# ZHSD-POWER.net
KiCad netlist of a schematic drawn in Altium Designer
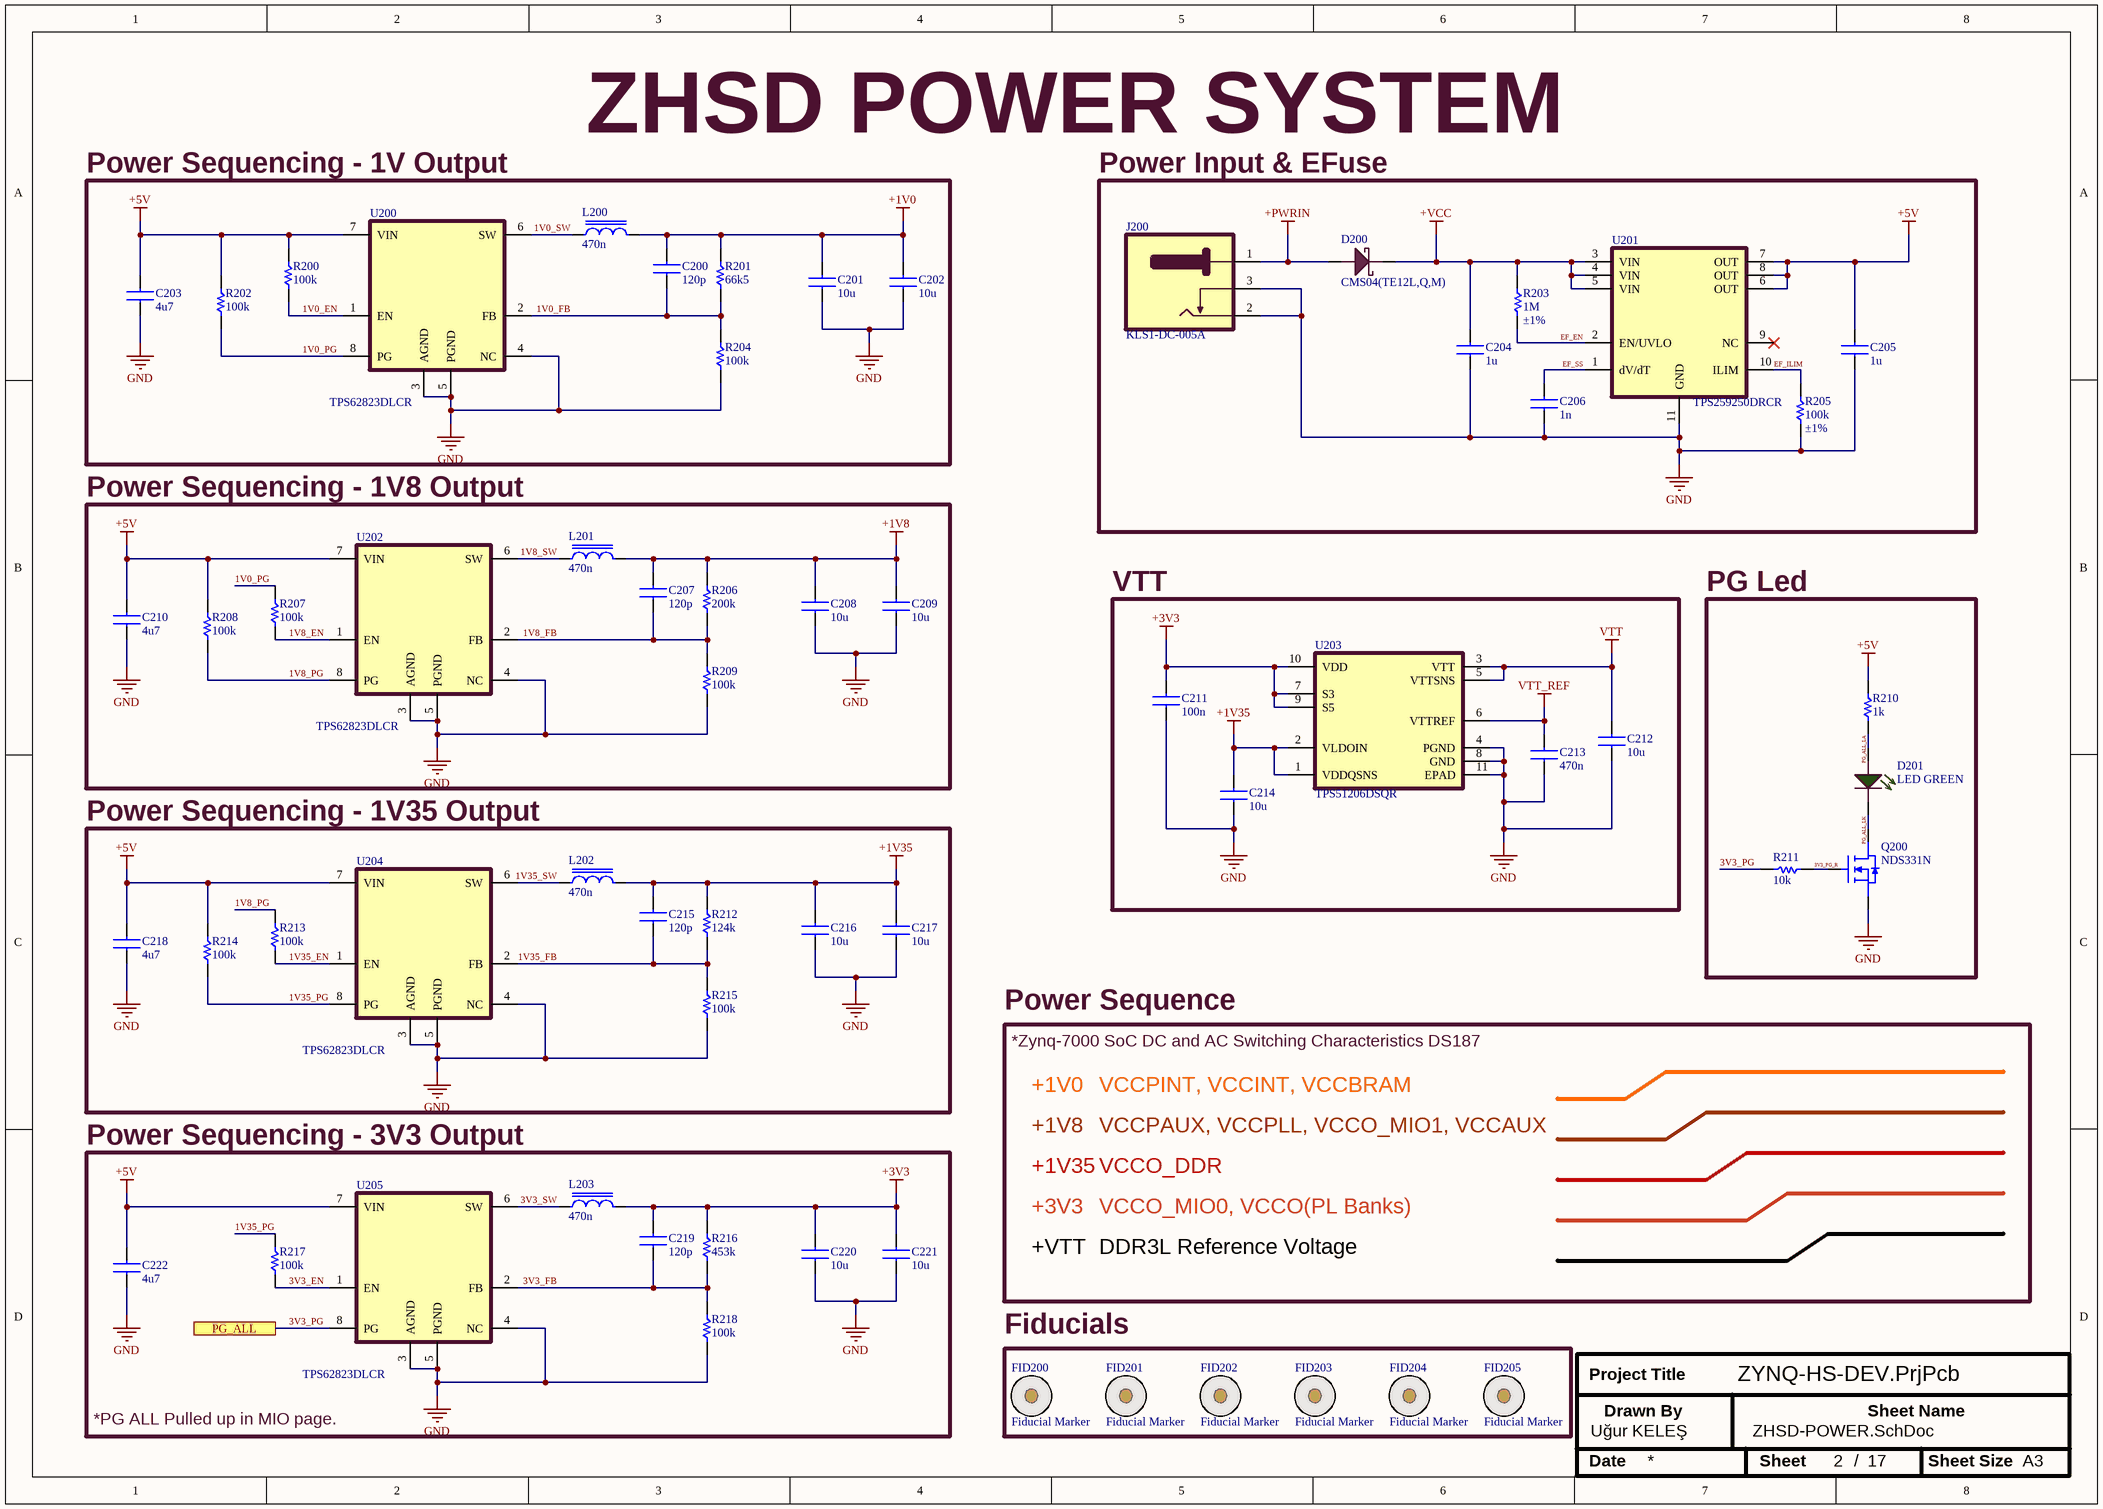
[diagram p0: ZHSD-POWER.SchDoc]

(export (version "E")
  (design (tool "Eeschema 10.0.6"))
  (components
    (comp (ref "C200")
      (value "120p")
      (footprint "0603CAPC1608X09N")
      (description "CAP CER 120PF 50V C0G/NP0 0603 (1608) ±5%")
      (fields (field (name "MANUFACTURER") "Murata Electronics") (field (name "MPN") "GRM1885C1H121JA01D"))
      (libsource (lib "UK_Library") (part "GRM1885C1H121JA01D"))
    )
    (comp (ref "C201")
      (value "10u")
      (footprint "0603CAPC1608X09N")
      (description "CAP CER 10UF 10V X7R 0603 (1608) ±20%")
      (fields (field (name "MANUFACTURER") "Murata Electronics") (field (name "MPN") "GRM188Z71A106MA73D"))
      (libsource (lib "UK_Library") (part "GRM188Z71A106MA73D"))
    )
    (comp (ref "C202")
      (value "10u")
      (footprint "0603CAPC1608X09N")
      (description "CAP CER 10UF 10V X7R 0603 (1608) ±20%")
      (fields (field (name "MANUFACTURER") "Murata Electronics") (field (name "MPN") "GRM188Z71A106MA73D"))
      (libsource (lib "UK_Library") (part "GRM188Z71A106MA73D"))
    )
    (comp (ref "C203")
      (value "4u7")
      (footprint "0805CAPC2012X14N")
      (description "CAP CER 4.7UF 10V X7R 0805 (2012) ±10%")
      (fields (field (name "MANUFACTURER") "Murata Electronics") (field (name "MPN") "GRM21BR71A475KE51L"))
      (libsource (lib "UK_Library") (part "GRM21BR71A475KE51L"))
    )
    (comp (ref "C204")
      (value "1u")
      (footprint "0603CAPC1608X09N")
      (description "CAP CER 1UF 25V X5R 0603 (1608) ±10%")
      (fields
        (field (name "MANUFACTURER") "Murata Power Solutions Inc.")
        (field (name "MPN") "GRM188R61E105KA12D")
      )
      (libsource (lib "UK_Library") (part "GRM188R61E105KA12D"))
    )
    (comp (ref "C205")
      (value "1u")
      (footprint "0603CAPC1608X09N")
      (description "CAP CER 1UF 25V X5R 0603 (1608) ±10%")
      (fields
        (field (name "MANUFACTURER") "Murata Power Solutions Inc.")
        (field (name "MPN") "GRM188R61E105KA12D")
      )
      (libsource (lib "UK_Library") (part "GRM188R61E105KA12D"))
    )
    (comp (ref "C206")
      (value "1n")
      (footprint "0603CAPC1608X09N")
      (description "CAP CER 1000PF 50V X7R 0603 (1608) ±10%")
      (fields (field (name "MANUFACTURER") "Murata Electronics") (field (name "MPN") "GCM188R71H102KA37D"))
      (libsource (lib "UK_Library") (part "GCM188R71H102KA37D"))
    )
    (comp (ref "C207")
      (value "120p")
      (footprint "0603CAPC1608X09N")
      (description "CAP CER 120PF 50V C0G/NP0 0603 (1608) ±5%")
      (fields (field (name "MANUFACTURER") "Murata Electronics") (field (name "MPN") "GRM1885C1H121JA01D"))
      (libsource (lib "UK_Library") (part "GRM1885C1H121JA01D"))
    )
    (comp (ref "C208")
      (value "10u")
      (footprint "0603CAPC1608X09N")
      (description "CAP CER 10UF 10V X7R 0603 (1608) ±20%")
      (fields (field (name "MANUFACTURER") "Murata Electronics") (field (name "MPN") "GRM188Z71A106MA73D"))
      (libsource (lib "UK_Library") (part "GRM188Z71A106MA73D"))
    )
    (comp (ref "C209")
      (value "10u")
      (footprint "0603CAPC1608X09N")
      (description "CAP CER 10UF 10V X7R 0603 (1608) ±20%")
      (fields (field (name "MANUFACTURER") "Murata Electronics") (field (name "MPN") "GRM188Z71A106MA73D"))
      (libsource (lib "UK_Library") (part "GRM188Z71A106MA73D"))
    )
    (comp (ref "C210")
      (value "4u7")
      (footprint "0805CAPC2012X14N")
      (description "CAP CER 4.7UF 10V X7R 0805 (2012) ±10%")
      (fields (field (name "MANUFACTURER") "Murata Electronics") (field (name "MPN") "GRM21BR71A475KE51L"))
      (libsource (lib "UK_Library") (part "GRM21BR71A475KE51L"))
    )
    (comp (ref "C211")
      (value "100n")
      (footprint "0402CAPC1005X06N")
      (description "CAP CER 0.1UF 16V X7R 0402 (1005) ±10%")
      (fields (field (name "MANUFACTURER") "Murata Electronics") (field (name "MPN") "GRM155R71C104KA88J"))
      (libsource (lib "UK_Library_SCH") (part "GRM155R71C104KA88J"))
    )
    (comp (ref "C212")
      (value "10u")
      (footprint "0603CAPC1608X09N")
      (description "CAP CER 10UF 10V X7R 0603 (1608) ±20%")
      (fields (field (name "MANUFACTURER") "Murata Electronics") (field (name "MPN") "GRM188Z71A106MA73D"))
      (libsource (lib "UK_Library") (part "GRM188Z71A106MA73D"))
    )
    (comp (ref "C213")
      (value "470n")
      (footprint "0402CAPC1005X06N")
      (description "CAP CER 0.47UF 6.3V X5R 0402(1005) ±10%")
      (fields (field (name "MANUFACTURER") "Murata Electronics") (field (name "MPN") "GRM155R60J474KE19D"))
      (libsource (lib "UK_Library") (part "GRM155R60J474KE19D"))
    )
    (comp (ref "C214")
      (value "10u")
      (footprint "0603CAPC1608X09N")
      (description "CAP CER 10UF 10V X7R 0603 (1608) ±20%")
      (fields (field (name "MANUFACTURER") "Murata Electronics") (field (name "MPN") "GRM188Z71A106MA73D"))
      (libsource (lib "UK_Library") (part "GRM188Z71A106MA73D"))
    )
    (comp (ref "C215")
      (value "120p")
      (footprint "0603CAPC1608X09N")
      (description "CAP CER 120PF 50V C0G/NP0 0603 (1608) ±5%")
      (fields (field (name "MANUFACTURER") "Murata Electronics") (field (name "MPN") "GRM1885C1H121JA01D"))
      (libsource (lib "UK_Library") (part "GRM1885C1H121JA01D"))
    )
    (comp (ref "C216")
      (value "10u")
      (footprint "0603CAPC1608X09N")
      (description "CAP CER 10UF 10V X7R 0603 (1608) ±20%")
      (fields (field (name "MANUFACTURER") "Murata Electronics") (field (name "MPN") "GRM188Z71A106MA73D"))
      (libsource (lib "UK_Library") (part "GRM188Z71A106MA73D"))
    )
    (comp (ref "C217")
      (value "10u")
      (footprint "0603CAPC1608X09N")
      (description "CAP CER 10UF 10V X7R 0603 (1608) ±20%")
      (fields (field (name "MANUFACTURER") "Murata Electronics") (field (name "MPN") "GRM188Z71A106MA73D"))
      (libsource (lib "UK_Library") (part "GRM188Z71A106MA73D"))
    )
    (comp (ref "C218")
      (value "4u7")
      (footprint "0805CAPC2012X14N")
      (description "CAP CER 4.7UF 10V X7R 0805 (2012) ±10%")
      (fields (field (name "MANUFACTURER") "Murata Electronics") (field (name "MPN") "GRM21BR71A475KE51L"))
      (libsource (lib "UK_Library") (part "GRM21BR71A475KE51L"))
    )
    (comp (ref "C219")
      (value "120p")
      (footprint "0603CAPC1608X09N")
      (description "CAP CER 120PF 50V C0G/NP0 0603 (1608) ±5%")
      (fields (field (name "MANUFACTURER") "Murata Electronics") (field (name "MPN") "GRM1885C1H121JA01D"))
      (libsource (lib "UK_Library") (part "GRM1885C1H121JA01D"))
    )
    (comp (ref "C220")
      (value "10u")
      (footprint "0603CAPC1608X09N")
      (description "CAP CER 10UF 10V X7R 0603 (1608) ±20%")
      (fields (field (name "MANUFACTURER") "Murata Electronics") (field (name "MPN") "GRM188Z71A106MA73D"))
      (libsource (lib "UK_Library") (part "GRM188Z71A106MA73D"))
    )
    (comp (ref "C221")
      (value "10u")
      (footprint "0603CAPC1608X09N")
      (description "CAP CER 10UF 10V X7R 0603 (1608) ±20%")
      (fields (field (name "MANUFACTURER") "Murata Electronics") (field (name "MPN") "GRM188Z71A106MA73D"))
      (libsource (lib "UK_Library") (part "GRM188Z71A106MA73D"))
    )
    (comp (ref "C222")
      (value "4u7")
      (footprint "0805CAPC2012X14N")
      (description "CAP CER 4.7UF 10V X7R 0805 (2012) ±10%")
      (fields (field (name "MANUFACTURER") "Murata Electronics") (field (name "MPN") "GRM21BR71A475KE51L"))
      (libsource (lib "UK_Library") (part "GRM21BR71A475KE51L"))
    )
    (comp (ref "D200")
      (value "CMS04(TE12L,Q,M)")
      (footprint "SOD-128")
      (description "Diode 30 V 5A Surface Mount M-FLAT (2.4x3.8)")
      (fields
        (field (name "MANUFACTURER") "Toshiba Semiconductor and Storage")
        (field (name "MPN") "CMS04(TE12L,Q")
      )
      (libsource (lib "UK_Library") (part "CMS04"))
    )
    (comp (ref "D201")
      (value "LED GREEN")
      (footprint "0603_LED_1608N")
      (description "LED GREEN CLEAR CHIP SMD")
      (fields (field (name "MANUFACTURER") "Lite-On Inc.") (field (name "MPN") "LTST-C191TGKT"))
      (libsource (lib "UK_Library") (part "LTST-C191TGKT"))
    )
    (comp (ref "FID200")
      (value "Fiducial Marker")
      (footprint "Fiducial")
      (description "Fiducial Marker 1mm No Bom")
      (libsource (lib "UK_Library") (part "Fiducial_Marker"))
    )
    (comp (ref "FID201")
      (value "Fiducial Marker")
      (footprint "Fiducial")
      (description "Fiducial Marker 1mm No Bom")
      (libsource (lib "UK_Library") (part "Fiducial_Marker"))
    )
    (comp (ref "FID202")
      (value "Fiducial Marker")
      (footprint "Fiducial")
      (description "Fiducial Marker 1mm No Bom")
      (libsource (lib "UK_Library") (part "Fiducial_Marker"))
    )
    (comp (ref "FID203")
      (value "Fiducial Marker")
      (footprint "Fiducial")
      (description "Fiducial Marker 1mm No Bom")
      (libsource (lib "UK_Library") (part "Fiducial_Marker"))
    )
    (comp (ref "FID204")
      (value "Fiducial Marker")
      (footprint "Fiducial")
      (description "Fiducial Marker 1mm No Bom")
      (libsource (lib "UK_Library") (part "Fiducial_Marker"))
    )
    (comp (ref "FID205")
      (value "Fiducial Marker")
      (footprint "Fiducial")
      (description "Fiducial Marker 1mm No Bom")
      (libsource (lib "UK_Library") (part "Fiducial_Marker"))
    )
    (comp (ref "J200")
      (value "KLS1-DC-005A")
      (footprint "CONN-KLS1-DC-005A")
      (description "CONNECTOR DC JACK POWER PCB TYPE 2.50MM KLS")
      (fields (field (name "MANUFACTURER") "KLS ELECTRONIC") (field (name "MPN") "L-KLS1-DC-005A-2.0"))
      (libsource (lib "UK_Library") (part "KLS1-DC-005A"))
    )
    (comp (ref "L200")
      (value "470n")
      (footprint "0806INDC2016X10N")
      (description "FIXED IND 470NH 3.6A 32 MOHM SMD 0806 (2016 Metric)")
      (fields (field (name "MANUFACTURER") "Murata Electronics") (field (name "MPN") "DFE201610E-R47M=P2"))
      (libsource (lib "UK_Library") (part "DFE201610E-R47M=P2"))
    )
    (comp (ref "L201")
      (value "470n")
      (footprint "0806INDC2016X10N")
      (description "FIXED IND 470NH 3.6A 32 MOHM SMD 0806 (2016 Metric)")
      (fields (field (name "MANUFACTURER") "Murata Electronics") (field (name "MPN") "DFE201610E-R47M=P2"))
      (libsource (lib "UK_Library") (part "DFE201610E-R47M=P2"))
    )
    (comp (ref "L202")
      (value "470n")
      (footprint "0806INDC2016X10N")
      (description "FIXED IND 470NH 3.6A 32 MOHM SMD 0806 (2016 Metric)")
      (fields (field (name "MANUFACTURER") "Murata Electronics") (field (name "MPN") "DFE201610E-R47M=P2"))
      (libsource (lib "UK_Library") (part "DFE201610E-R47M=P2"))
    )
    (comp (ref "L203")
      (value "470n")
      (footprint "0806INDC2016X10N")
      (description "FIXED IND 470NH 3.6A 32 MOHM SMD 0806 (2016 Metric)")
      (fields (field (name "MANUFACTURER") "Murata Electronics") (field (name "MPN") "DFE201610E-R47M=P2"))
      (libsource (lib "UK_Library") (part "DFE201610E-R47M=P2"))
    )
    (comp (ref "Q200")
      (value "NDS331N")
      (footprint "SOT95P251X112-3N")
      (description "N-Channel 20 V 1.3A (Ta) 500mW (Ta) Surface Mount SOT-23-3")
      (fields (field (name "MANUFACTURER") "onsemi"))
      (libsource (lib "UK_Library") (part "NDS331N"))
    )
    (comp (ref "R200")
      (value "100k")
      (footprint "0603RESC1608X05L")
      (description "RES SMD 100K OHM 1% 1/8W 0603 (1608)")
      (fields (field (name "MANUFACTURER") "Vishay Dale") (field (name "MPN") "CRCW0603100KFKEA"))
      (libsource (lib "UK_Library") (part "CRCW0603100KFKEA"))
    )
    (comp (ref "R201")
      (value "66k5")
      (footprint "0603RESC1608X05N")
      (description "RES SMD 66.5K OHM 1% 1/8W 0603 (1608)")
      (fields (field (name "MANUFACTURER") "Vishay Dale") (field (name "MPN") "CRCW060366K5FKEA"))
      (libsource (lib "UK_Library") (part "CRCW060366K5FKEA"))
    )
    (comp (ref "R202")
      (value "100k")
      (footprint "0603RESC1608X05L")
      (description "RES SMD 100K OHM 1% 1/8W 0603 (1608)")
      (fields (field (name "MANUFACTURER") "Vishay Dale") (field (name "MPN") "CRCW0603100KFKEA"))
      (libsource (lib "UK_Library") (part "CRCW0603100KFKEA"))
    )
    (comp (ref "R203")
      (value "1M")
      (footprint "0603RESC1608X05N")
      (description "RES SMD 1M OHM 1% 1/8W 0603 (1608)")
      (fields
        (field (name "MANUFACTURER") "Vishay Dale")
        (field (name "MPN") "CRCW06031M00FKEA")
        (field (name "TOLERANCE") "±1%")
      )
      (libsource (lib "UK_Library") (part "CRCW06031M00FKEA"))
    )
    (comp (ref "R204")
      (value "100k")
      (footprint "0603RESC1608X05L")
      (description "RES SMD 100K OHM 1% 1/8W 0603 (1608)")
      (fields (field (name "MANUFACTURER") "Vishay Dale") (field (name "MPN") "CRCW0603100KFKEA"))
      (libsource (lib "UK_Library") (part "CRCW0603100KFKEA"))
    )
    (comp (ref "R205")
      (value "100k")
      (footprint "0603RESC1608X05L")
      (description "RES SMD 100K OHM 1% 1/8W 0603 (1608)")
      (fields
        (field (name "MANUFACTURER") "Vishay Dale")
        (field (name "MPN") "CRCW0603100KFKEA")
        (field (name "TOLERANCE") "±1%")
      )
      (libsource (lib "UK_Library") (part "CRCW0603100KFKEA"))
    )
    (comp (ref "R206")
      (value "200k")
      (footprint "0603RESC1608X05N")
      (description "RES 200K OHM 1% 1/10W 0603 (1608)")
      (fields (field (name "MANUFACTURER") "Vishay Dale") (field (name "MPN") "CRCW0603200KFKEBC"))
      (libsource (lib "UK_Library") (part "CRCW0603200KFKEBC"))
    )
    (comp (ref "R207")
      (value "100k")
      (footprint "0603RESC1608X05L")
      (description "RES SMD 100K OHM 1% 1/8W 0603 (1608)")
      (fields (field (name "MANUFACTURER") "Vishay Dale") (field (name "MPN") "CRCW0603100KFKEA"))
      (libsource (lib "UK_Library") (part "CRCW0603100KFKEA"))
    )
    (comp (ref "R208")
      (value "100k")
      (footprint "0603RESC1608X05L")
      (description "RES SMD 100K OHM 1% 1/8W 0603 (1608)")
      (fields (field (name "MANUFACTURER") "Vishay Dale") (field (name "MPN") "CRCW0603100KFKEA"))
      (libsource (lib "UK_Library") (part "CRCW0603100KFKEA"))
    )
    (comp (ref "R209")
      (value "100k")
      (footprint "0603RESC1608X05L")
      (description "RES SMD 100K OHM 1% 1/8W 0603 (1608)")
      (fields (field (name "MANUFACTURER") "Vishay Dale") (field (name "MPN") "CRCW0603100KFKEA"))
      (libsource (lib "UK_Library") (part "CRCW0603100KFKEA"))
    )
    (comp (ref "R210")
      (value "1k")
      (footprint "0402RESC1005X04N")
      (description "RES 1K OHM 5% 1/16W 0402 (1005)")
      (fields (field (name "MANUFACTURER") "YAGEO") (field (name "MPN") "RC0402JR-071KL"))
      (libsource (lib "UK_Library") (part "RC0402JR-071KL"))
    )
    (comp (ref "R211")
      (value "10k")
      (footprint "0603RESC1608X05N")
      (description "RES 10K OHM 1% 1/10W 0603(1608)")
      (fields (field (name "MANUFACTURER") "YAGEO") (field (name "MPN") "RC0603FR-0710KL"))
      (libsource (lib "UK_Library") (part "RC0603FR-0710KL"))
    )
    (comp (ref "R212")
      (value "124k")
      (footprint "0603RESC1608X05N")
      (description "RES SMD 124K OHM 1% 1/8W 0603 (1608)")
      (fields (field (name "MANUFACTURER") "Vishay Dale") (field (name "MPN") "CRCW0603124KFKEA"))
      (libsource (lib "UK_Library") (part "CRCW0603124KFKEA"))
    )
    (comp (ref "R213")
      (value "100k")
      (footprint "0603RESC1608X05L")
      (description "RES SMD 100K OHM 1% 1/8W 0603 (1608)")
      (fields (field (name "MANUFACTURER") "Vishay Dale") (field (name "MPN") "CRCW0603100KFKEA"))
      (libsource (lib "UK_Library") (part "CRCW0603100KFKEA"))
    )
    (comp (ref "R214")
      (value "100k")
      (footprint "0603RESC1608X05L")
      (description "RES SMD 100K OHM 1% 1/8W 0603 (1608)")
      (fields (field (name "MANUFACTURER") "Vishay Dale") (field (name "MPN") "CRCW0603100KFKEA"))
      (libsource (lib "UK_Library") (part "CRCW0603100KFKEA"))
    )
    (comp (ref "R215")
      (value "100k")
      (footprint "0603RESC1608X05L")
      (description "RES SMD 100K OHM 1% 1/8W 0603 (1608)")
      (fields (field (name "MANUFACTURER") "Vishay Dale") (field (name "MPN") "CRCW0603100KFKEA"))
      (libsource (lib "UK_Library") (part "CRCW0603100KFKEA"))
    )
    (comp (ref "R216")
      (value "453k")
      (footprint "0603RESC1608X05N")
      (description "RES 453K OHM 1% 1/10W 0603(1608)")
      (fields (field (name "MANUFACTURER") "Vishay Dale") (field (name "MPN") "CRCW0603453KFKEAC"))
      (libsource (lib "UK_Library") (part "CRCW0603453KFKEAC"))
    )
    (comp (ref "R217")
      (value "100k")
      (footprint "0603RESC1608X05L")
      (description "RES SMD 100K OHM 1% 1/8W 0603 (1608)")
      (fields (field (name "MANUFACTURER") "Vishay Dale") (field (name "MPN") "CRCW0603100KFKEA"))
      (libsource (lib "UK_Library") (part "CRCW0603100KFKEA"))
    )
    (comp (ref "R218")
      (value "100k")
      (footprint "0603RESC1608X05L")
      (description "RES SMD 100K OHM 1% 1/8W 0603 (1608)")
      (fields (field (name "MANUFACTURER") "Vishay Dale") (field (name "MPN") "CRCW0603100KFKEA"))
      (libsource (lib "UK_Library") (part "CRCW0603100KFKEA"))
    )
    (comp (ref "U200")
      (value "TPS62823DLCR")
      (footprint "VSON50P150X100-8N")
      (description "2.4-V to 5.5-V input, 3-A step-down converter with 1% accuracy in 1.5-mm x 2-mm VSON-HR package")
      (fields (field (name "MANUFACTURER") "Texas Instruments"))
      (libsource (lib "UK_Library") (part "TPS62823DLCR"))
    )
    (comp (ref "U201")
      (value "TPS259250DRCR")
      (footprint "VSON50P300X100_HS-11N")
      (description "Electronic Fuse Regulator 5A 10-VSON (3x3)")
      (fields (field (name "MANUFACTURER") "Texas Instruments"))
      (libsource (lib "UK_Library") (part "TPS259250DRCR"))
    )
    (comp (ref "U202")
      (value "TPS62823DLCR")
      (footprint "VSON50P150X100-8N")
      (description "2.4-V to 5.5-V input, 3-A step-down converter with 1% accuracy in 1.5-mm x 2-mm VSON-HR package")
      (fields (field (name "MANUFACTURER") "Texas Instruments"))
      (libsource (lib "UK_Library") (part "TPS62823DLCR"))
    )
    (comp (ref "U203")
      (value "TPS51206DSQR")
      (footprint "WSON2X2-10/SON40P200X80_HS-11N")
      (description "Converter, DDR Voltage Regulator IC 1 Output 10-WSON (2x2)")
      (fields (field (name "MANUFACTURER") "Texas Instruments"))
      (libsource (lib "UK_Library") (part "TPS51206"))
    )
    (comp (ref "U204")
      (value "TPS62823DLCR")
      (footprint "VSON50P150X100-8N")
      (description "2.4-V to 5.5-V input, 3-A step-down converter with 1% accuracy in 1.5-mm x 2-mm VSON-HR package")
      (fields (field (name "MANUFACTURER") "Texas Instruments"))
      (libsource (lib "UK_Library") (part "TPS62823DLCR"))
    )
    (comp (ref "U205")
      (value "TPS62823DLCR")
      (footprint "VSON50P150X100-8N")
      (description "2.4-V to 5.5-V input, 3-A step-down converter with 1% accuracy in 1.5-mm x 2-mm VSON-HR package")
      (fields (field (name "MANUFACTURER") "Texas Instruments"))
      (libsource (lib "UK_Library") (part "TPS62823DLCR"))
    )
  )
  (nets
    (net (code "1") (name "+1V0") (class "Default")
      (node (ref "C200") (pin "2") (pinfunction "2_2") (pintype "passive"))
      (node (ref "C201") (pin "2") (pinfunction "2_2") (pintype "passive"))
      (node (ref "C202") (pin "2") (pinfunction "2_2") (pintype "passive"))
      (node (ref "L200") (pin "2") (pinfunction "2_2") (pintype "passive"))
      (node (ref "R201") (pin "2") (pinfunction "2_2") (pintype "passive"))
    )
    (net (code "2") (name "+1V8") (class "Default")
      (node (ref "C207") (pin "2") (pinfunction "2_2") (pintype "passive"))
      (node (ref "C208") (pin "2") (pinfunction "2_2") (pintype "passive"))
      (node (ref "C209") (pin "2") (pinfunction "2_2") (pintype "passive"))
      (node (ref "L201") (pin "2") (pinfunction "2_2") (pintype "passive"))
      (node (ref "R206") (pin "2") (pinfunction "2_2") (pintype "passive"))
    )
    (net (code "3") (name "+1V35") (class "Default")
      (node (ref "C214") (pin "2") (pinfunction "2_2") (pintype "passive"))
      (node (ref "C215") (pin "2") (pinfunction "2_2") (pintype "passive"))
      (node (ref "C216") (pin "2") (pinfunction "2_2") (pintype "passive"))
      (node (ref "C217") (pin "2") (pinfunction "2_2") (pintype "passive"))
      (node (ref "L202") (pin "2") (pinfunction "2_2") (pintype "passive"))
      (node (ref "R212") (pin "2") (pinfunction "2_2") (pintype "passive"))
      (node (ref "U203") (pin "1") (pinfunction "VDDQSNS_1") (pintype "power_in"))
      (node (ref "U203") (pin "2") (pinfunction "VLDOIN_2") (pintype "power_in"))
    )
    (net (code "4") (name "+3V3") (class "Default")
      (node (ref "C211") (pin "2") (pinfunction "2_2") (pintype "passive"))
      (node (ref "C219") (pin "2") (pinfunction "2_2") (pintype "passive"))
      (node (ref "C220") (pin "2") (pinfunction "2_2") (pintype "passive"))
      (node (ref "C221") (pin "2") (pinfunction "2_2") (pintype "passive"))
      (node (ref "L203") (pin "2") (pinfunction "2_2") (pintype "passive"))
      (node (ref "R216") (pin "2") (pinfunction "2_2") (pintype "passive"))
      (node (ref "U203") (pin "10") (pinfunction "VDD_10") (pintype "power_in"))
      (node (ref "U203") (pin "7") (pinfunction "S3_7") (pintype "power_in"))
      (node (ref "U203") (pin "9") (pinfunction "S5_9") (pintype "power_in"))
    )
    (net (code "5") (name "+5V") (class "Default")
      (node (ref "C203") (pin "2") (pinfunction "2_2") (pintype "passive"))
      (node (ref "C205") (pin "2") (pinfunction "2_2") (pintype "passive"))
      (node (ref "C210") (pin "2") (pinfunction "2_2") (pintype "passive"))
      (node (ref "C218") (pin "2") (pinfunction "2_2") (pintype "passive"))
      (node (ref "C222") (pin "2") (pinfunction "2_2") (pintype "passive"))
      (node (ref "R200") (pin "2") (pinfunction "2_2") (pintype "passive"))
      (node (ref "R202") (pin "2") (pinfunction "2_2") (pintype "passive"))
      (node (ref "R208") (pin "2") (pinfunction "2_2") (pintype "passive"))
      (node (ref "R210") (pin "2") (pinfunction "2_2") (pintype "passive"))
      (node (ref "R214") (pin "2") (pinfunction "2_2") (pintype "passive"))
      (node (ref "U200") (pin "7") (pinfunction "VIN_7") (pintype "power_in"))
      (node (ref "U201") (pin "6") (pinfunction "OUT_6") (pintype "power_in"))
      (node (ref "U201") (pin "7") (pinfunction "OUT_7") (pintype "power_in"))
      (node (ref "U201") (pin "8") (pinfunction "OUT_8") (pintype "power_in"))
      (node (ref "U202") (pin "7") (pinfunction "VIN_7") (pintype "power_in"))
      (node (ref "U204") (pin "7") (pinfunction "VIN_7") (pintype "power_in"))
      (node (ref "U205") (pin "7") (pinfunction "VIN_7") (pintype "power_in"))
    )
    (net (code "6") (name "+PWRIN") (class "Default")
      (node (ref "D200") (pin "A") (pinfunction "2_A") (pintype "passive"))
      (node (ref "J200") (pin "1") (pinfunction "VCC_1") (pintype "passive"))
    )
    (net (code "7") (name "+VCC") (class "Default")
      (node (ref "C204") (pin "2") (pinfunction "2_2") (pintype "passive"))
      (node (ref "D200") (pin "C") (pinfunction "1_C") (pintype "passive"))
      (node (ref "R203") (pin "1") (pinfunction "1_1") (pintype "passive"))
      (node (ref "U201") (pin "3") (pinfunction "VIN_3") (pintype "power_in"))
      (node (ref "U201") (pin "4") (pinfunction "VIN_4") (pintype "power_in"))
      (node (ref "U201") (pin "5") (pinfunction "VIN_5") (pintype "power_in"))
    )
    (net (code "8") (name "/1V0_EN") (class "Default")
      (node (ref "R200") (pin "1") (pinfunction "1_1") (pintype "passive"))
      (node (ref "U200") (pin "1") (pinfunction "EN_1") (pintype "passive"))
    )
    (net (code "9") (name "/1V0_FB") (class "Default")
      (node (ref "C200") (pin "1") (pinfunction "1_1") (pintype "passive"))
      (node (ref "R201") (pin "1") (pinfunction "1_1") (pintype "passive"))
      (node (ref "R204") (pin "2") (pinfunction "2_2") (pintype "passive"))
      (node (ref "U200") (pin "2") (pinfunction "FB_2") (pintype "passive"))
    )
    (net (code "10") (name "/1V0_PG") (class "Default")
      (node (ref "R202") (pin "1") (pinfunction "1_1") (pintype "passive"))
      (node (ref "R207") (pin "2") (pinfunction "2_2") (pintype "passive"))
      (node (ref "U200") (pin "8") (pinfunction "PG_8") (pintype "passive"))
    )
    (net (code "11") (name "/1V0_SW") (class "Default")
      (node (ref "L200") (pin "1") (pinfunction "1_1") (pintype "passive"))
      (node (ref "U200") (pin "6") (pinfunction "SW_6") (pintype "power_in"))
    )
    (net (code "12") (name "/1V8_EN") (class "Default")
      (node (ref "R207") (pin "1") (pinfunction "1_1") (pintype "passive"))
      (node (ref "U202") (pin "1") (pinfunction "EN_1") (pintype "passive"))
    )
    (net (code "13") (name "/1V8_FB") (class "Default")
      (node (ref "C207") (pin "1") (pinfunction "1_1") (pintype "passive"))
      (node (ref "R206") (pin "1") (pinfunction "1_1") (pintype "passive"))
      (node (ref "R209") (pin "2") (pinfunction "2_2") (pintype "passive"))
      (node (ref "U202") (pin "2") (pinfunction "FB_2") (pintype "passive"))
    )
    (net (code "14") (name "/1V8_PG") (class "Default")
      (node (ref "R208") (pin "1") (pinfunction "1_1") (pintype "passive"))
      (node (ref "R213") (pin "2") (pinfunction "2_2") (pintype "passive"))
      (node (ref "U202") (pin "8") (pinfunction "PG_8") (pintype "passive"))
    )
    (net (code "15") (name "/1V8_SW") (class "Default")
      (node (ref "L201") (pin "1") (pinfunction "1_1") (pintype "passive"))
      (node (ref "U202") (pin "6") (pinfunction "SW_6") (pintype "power_in"))
    )
    (net (code "16") (name "/1V35_EN") (class "Default")
      (node (ref "R213") (pin "1") (pinfunction "1_1") (pintype "passive"))
      (node (ref "U204") (pin "1") (pinfunction "EN_1") (pintype "passive"))
    )
    (net (code "17") (name "/1V35_FB") (class "Default")
      (node (ref "C215") (pin "1") (pinfunction "1_1") (pintype "passive"))
      (node (ref "R212") (pin "1") (pinfunction "1_1") (pintype "passive"))
      (node (ref "R215") (pin "2") (pinfunction "2_2") (pintype "passive"))
      (node (ref "U204") (pin "2") (pinfunction "FB_2") (pintype "passive"))
    )
    (net (code "18") (name "/1V35_PG") (class "Default")
      (node (ref "R214") (pin "1") (pinfunction "1_1") (pintype "passive"))
      (node (ref "R217") (pin "2") (pinfunction "2_2") (pintype "passive"))
      (node (ref "U204") (pin "8") (pinfunction "PG_8") (pintype "passive"))
    )
    (net (code "19") (name "/1V35_SW") (class "Default")
      (node (ref "L202") (pin "1") (pinfunction "1_1") (pintype "passive"))
      (node (ref "U204") (pin "6") (pinfunction "SW_6") (pintype "power_in"))
    )
    (net (code "20") (name "/3V3_EN") (class "Default")
      (node (ref "R217") (pin "1") (pinfunction "1_1") (pintype "passive"))
      (node (ref "U205") (pin "1") (pinfunction "EN_1") (pintype "passive"))
    )
    (net (code "21") (name "/3V3_FB") (class "Default")
      (node (ref "C219") (pin "1") (pinfunction "1_1") (pintype "passive"))
      (node (ref "R216") (pin "1") (pinfunction "1_1") (pintype "passive"))
      (node (ref "R218") (pin "2") (pinfunction "2_2") (pintype "passive"))
      (node (ref "U205") (pin "2") (pinfunction "FB_2") (pintype "passive"))
    )
    (net (code "22") (name "/3V3_PG") (class "Default")
      (node (ref "R211") (pin "2") (pinfunction "2_2") (pintype "passive"))
      (node (ref "U205") (pin "8") (pinfunction "PG_8") (pintype "passive"))
    )
    (net (code "23") (name "/3V3_PG_R") (class "Default")
      (node (ref "Q200") (pin "1") (pinfunction "G_1") (pintype "passive"))
      (node (ref "R211") (pin "1") (pinfunction "1_1") (pintype "passive"))
    )
    (net (code "24") (name "/3V3_SW") (class "Default")
      (node (ref "L203") (pin "1") (pinfunction "1_1") (pintype "passive"))
      (node (ref "U205") (pin "6") (pinfunction "SW_6") (pintype "power_in"))
    )
    (net (code "25") (name "/EF_EN") (class "Default")
      (node (ref "R203") (pin "2") (pinfunction "2_2") (pintype "passive"))
      (node (ref "U201") (pin "2") (pinfunction "EN/UVLO_2") (pintype "passive"))
    )
    (net (code "26") (name "/EF_ILIM") (class "Default")
      (node (ref "R205") (pin "2") (pinfunction "2_2") (pintype "passive"))
      (node (ref "U201") (pin "10") (pinfunction "ILIM_10") (pintype "passive"))
    )
    (net (code "27") (name "/EF_SS") (class "Default")
      (node (ref "C206") (pin "2") (pinfunction "2_2") (pintype "passive"))
      (node (ref "U201") (pin "1") (pinfunction "dV/dT_1") (pintype "passive"))
    )
    (net (code "28") (name "/PG_ALL_LA") (class "Default")
      (node (ref "D201") (pin "1") (pinfunction "A_1") (pintype "passive"))
      (node (ref "R210") (pin "1") (pinfunction "1_1") (pintype "passive"))
    )
    (net (code "29") (name "/PG_ALL_LK") (class "Default")
      (node (ref "D201") (pin "2") (pinfunction "C_2") (pintype "passive"))
      (node (ref "Q200") (pin "3") (pinfunction "D_3") (pintype "passive"))
    )
    (net (code "30") (name "GND") (class "Default")
      (node (ref "C201") (pin "1") (pinfunction "1_1") (pintype "passive"))
      (node (ref "C202") (pin "1") (pinfunction "1_1") (pintype "passive"))
      (node (ref "C203") (pin "1") (pinfunction "1_1") (pintype "passive"))
      (node (ref "C204") (pin "1") (pinfunction "1_1") (pintype "passive"))
      (node (ref "C205") (pin "1") (pinfunction "1_1") (pintype "passive"))
      (node (ref "C206") (pin "1") (pinfunction "1_1") (pintype "passive"))
      (node (ref "C208") (pin "1") (pinfunction "1_1") (pintype "passive"))
      (node (ref "C209") (pin "1") (pinfunction "1_1") (pintype "passive"))
      (node (ref "C210") (pin "1") (pinfunction "1_1") (pintype "passive"))
      (node (ref "C211") (pin "1") (pinfunction "1_1") (pintype "passive"))
      (node (ref "C212") (pin "1") (pinfunction "1_1") (pintype "passive"))
      (node (ref "C213") (pin "1") (pinfunction "1_1") (pintype "passive"))
      (node (ref "C214") (pin "1") (pinfunction "1_1") (pintype "passive"))
      (node (ref "C216") (pin "1") (pinfunction "1_1") (pintype "passive"))
      (node (ref "C217") (pin "1") (pinfunction "1_1") (pintype "passive"))
      (node (ref "C218") (pin "1") (pinfunction "1_1") (pintype "passive"))
      (node (ref "C220") (pin "1") (pinfunction "1_1") (pintype "passive"))
      (node (ref "C221") (pin "1") (pinfunction "1_1") (pintype "passive"))
      (node (ref "C222") (pin "1") (pinfunction "1_1") (pintype "passive"))
      (node (ref "J200") (pin "2") (pinfunction "GND_2") (pintype "passive"))
      (node (ref "J200") (pin "3") (pinfunction "SH_3") (pintype "passive"))
      (node (ref "Q200") (pin "2") (pinfunction "S_2") (pintype "passive"))
      (node (ref "R204") (pin "1") (pinfunction "1_1") (pintype "passive"))
      (node (ref "R205") (pin "1") (pinfunction "1_1") (pintype "passive"))
      (node (ref "R209") (pin "1") (pinfunction "1_1") (pintype "passive"))
      (node (ref "R215") (pin "1") (pinfunction "1_1") (pintype "passive"))
      (node (ref "R218") (pin "1") (pinfunction "1_1") (pintype "passive"))
      (node (ref "U200") (pin "3") (pinfunction "AGND_3") (pintype "power_in"))
      (node (ref "U200") (pin "4") (pinfunction "NC_4") (pintype "power_in"))
      (node (ref "U200") (pin "5") (pinfunction "PGND_5") (pintype "power_in"))
      (node (ref "U201") (pin "11") (pinfunction "GND_11") (pintype "power_in"))
      (node (ref "U202") (pin "3") (pinfunction "AGND_3") (pintype "power_in"))
      (node (ref "U202") (pin "4") (pinfunction "NC_4") (pintype "power_in"))
      (node (ref "U202") (pin "5") (pinfunction "PGND_5") (pintype "power_in"))
      (node (ref "U203") (pin "11") (pinfunction "EPAD_11") (pintype "power_in"))
      (node (ref "U203") (pin "4") (pinfunction "PGND_4") (pintype "power_in"))
      (node (ref "U203") (pin "8") (pinfunction "GND_8") (pintype "power_in"))
      (node (ref "U204") (pin "3") (pinfunction "AGND_3") (pintype "power_in"))
      (node (ref "U204") (pin "4") (pinfunction "NC_4") (pintype "power_in"))
      (node (ref "U204") (pin "5") (pinfunction "PGND_5") (pintype "power_in"))
      (node (ref "U205") (pin "3") (pinfunction "AGND_3") (pintype "power_in"))
      (node (ref "U205") (pin "4") (pinfunction "NC_4") (pintype "power_in"))
      (node (ref "U205") (pin "5") (pinfunction "PGND_5") (pintype "power_in"))
    )
    (net (code "31") (name "VTT") (class "Default")
      (node (ref "C212") (pin "2") (pinfunction "2_2") (pintype "passive"))
      (node (ref "U203") (pin "3") (pinfunction "VTT_3") (pintype "power_in"))
      (node (ref "U203") (pin "5") (pinfunction "VTTSNS_5") (pintype "power_in"))
    )
    (net (code "32") (name "VTT_REF") (class "Default")
      (node (ref "C213") (pin "2") (pinfunction "2_2") (pintype "passive"))
      (node (ref "U203") (pin "6") (pinfunction "VTTREF_6") (pintype "power_in"))
    )
    (net (code "33") (name "unconnected-(U201-NC-Pad9)") (class "Default")
      (node (ref "U201") (pin "9") (pinfunction "NC_9") (pintype "passive+no_connect"))
    )
  )
)
